# 01_power.net
KiCad netlist of a schematic drawn in Altium Designer
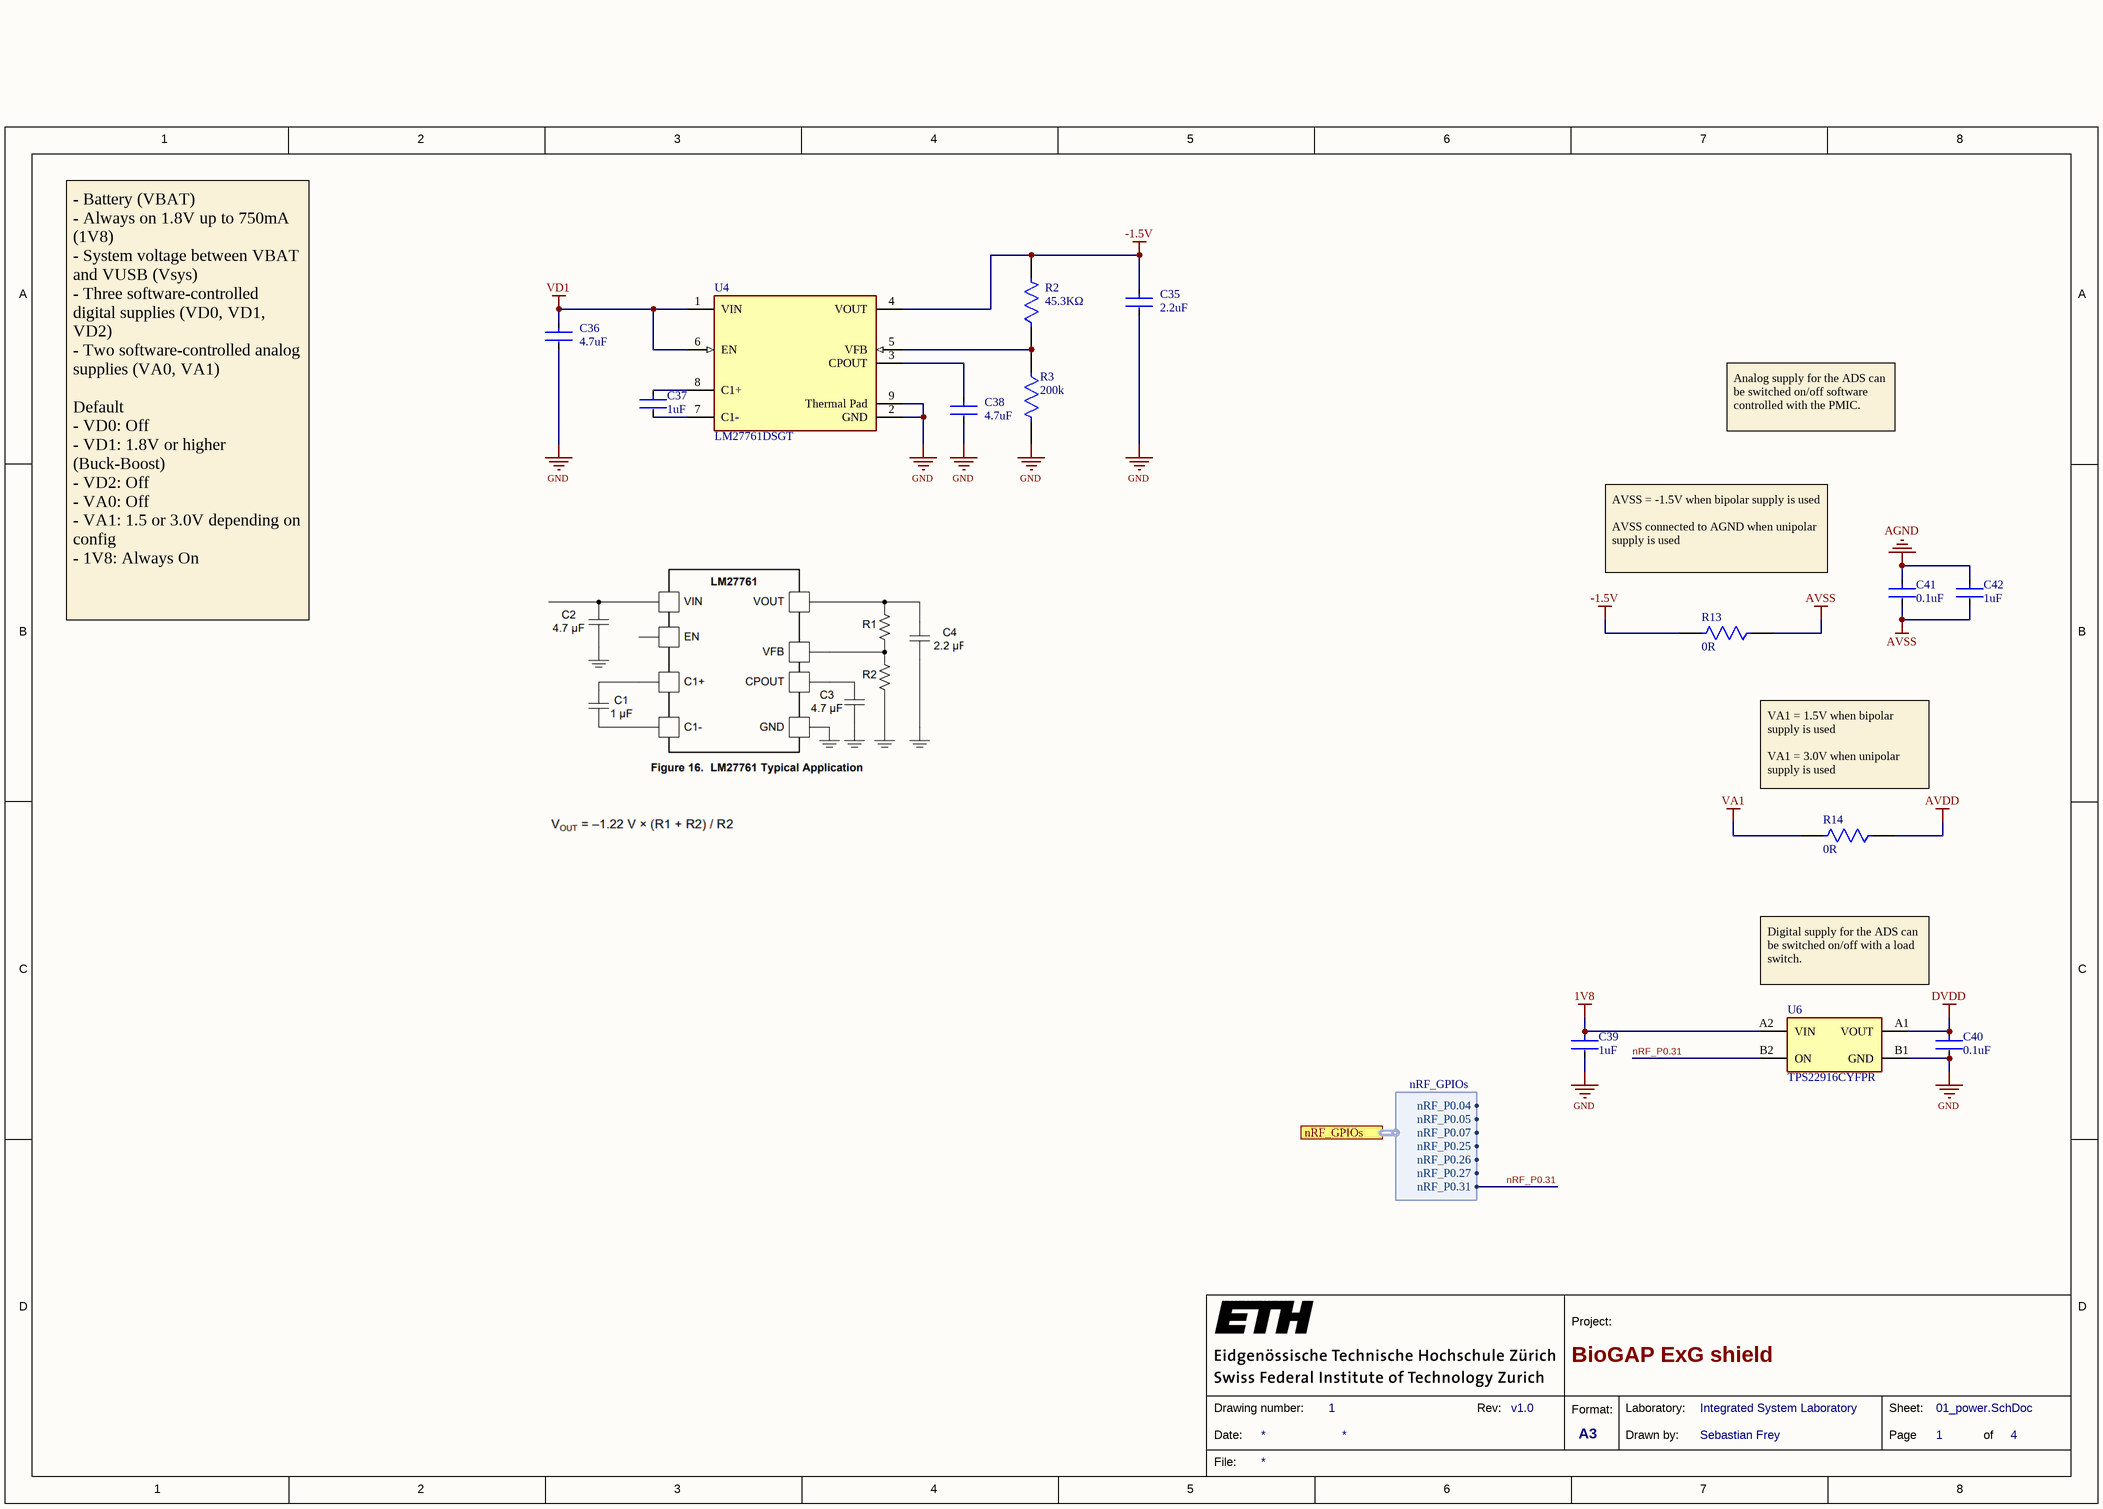
[diagram p0: 01_power.SchDoc]

(export (version "E")
  (design (tool "Eeschema 10.0.6"))
  (components
    (comp (ref "C35")
      (value "GRM155Z71A225KE01D")
      (footprint "FP-GRM155-0_15-IPC_B")
      (description "Chip Multilayer Ceramic Capacitors for General Purpose, 0402, 2.2uF, X7R, 15%, 10%, 10V")
      (fields (field (name "CAPACITANCE") "2.2uF"))
      (libsource (lib "Altium Content Vault") (part "b4654b650e69147ec39a6b967a45e02"))
    )
    (comp (ref "C36")
      (value "CL05A475MP5NRNC")
      (footprint "FP-CL282-IPC_C")
      (description "Cap Ceramic 4.7uF 10V X5R ±20% SMD 0402 +85°C Paper T/R")
      (fields (field (name "CAPACITANCE") "4.7uF") (field (name "TOLERANCE") "20%"))
      (libsource (lib "Altium Content Vault") (part "b4654b650e69147ec39a6b967a45e02"))
    )
    (comp (ref "C37")
      (value "CL05A105KP5NNNC")
      (footprint "FP-CL511-IPC_C")
      (description "Cap Ceramic 1uF 10V X5R ±10% SMD 0402 +85°C Paper T/R")
      (fields (field (name "CAPACITANCE") "1uF") (field (name "TOLERANCE") "10%"))
      (libsource (lib "Altium Content Vault") (part "b4654b650e69147ec39a6b967a45e02"))
    )
    (comp (ref "C38")
      (value "CL05A475MP5NRNC")
      (footprint "FP-CL282-IPC_C")
      (description "Cap Ceramic 4.7uF 10V X5R ±20% SMD 0402 +85°C Paper T/R")
      (fields (field (name "CAPACITANCE") "4.7uF") (field (name "TOLERANCE") "20%"))
      (libsource (lib "Altium Content Vault") (part "b4654b650e69147ec39a6b967a45e02"))
    )
    (comp (ref "C39")
      (value "CL05A105KP5NNNC")
      (footprint "FP-CL511-IPC_C")
      (description "Cap Ceramic 1uF 10V X5R ±10% SMD 0402 +85°C Paper T/R")
      (fields (field (name "CAPACITANCE") "1uF") (field (name "TOLERANCE") "10%"))
      (libsource (lib "Altium Content Vault") (part "b4654b650e69147ec39a6b967a45e02"))
    )
    (comp (ref "C40")
      (value "CL05A104KA5NNNC")
      (footprint "FP-CL278-IPC_C")
      (description "Cap Ceramic 100nF 25V X5R ±10% SMD 0402 +85°C Paper T/R")
      (fields
        (field (name "VOLTAGE") "25V")
        (field (name "TOLERANCE") "10%")
        (field (name "CAPACITANCE") "0.1uF")
      )
      (libsource (lib "Altium Content Vault") (part "b4654b650e69147ec39a6b967a45e02"))
    )
    (comp (ref "C41")
      (value "CL05A104KA5NNNC")
      (footprint "FP-CL278-IPC_C")
      (description "Cap Ceramic 100nF 25V X5R ±10% SMD 0402 +85°C Paper T/R")
      (fields
        (field (name "VOLTAGE") "25V")
        (field (name "TOLERANCE") "10%")
        (field (name "CAPACITANCE") "0.1uF")
      )
      (libsource (lib "Altium Content Vault") (part "b4654b650e69147ec39a6b967a45e02"))
    )
    (comp (ref "C42")
      (value "CL05A105KP5NNNC")
      (footprint "FP-CL511-IPC_C")
      (description "Cap Ceramic 1uF 10V X5R ±10% SMD 0402 +85°C Paper T/R")
      (fields (field (name "CAPACITANCE") "1uF") (field (name "TOLERANCE") "10%"))
      (libsource (lib "Altium Content Vault") (part "b4654b650e69147ec39a6b967a45e02"))
    )
    (comp (ref "R2")
      (value "RT0402BRD0745K3L")
      (footprint "FP-RT0402-MFG")
      (description "RES 45.3K OHM 1/16W .1% SMD 0402")
      (fields
        (field (name "RESISTANCE") "45.3KΩ")
        (field (name "MANUFACTURER") "Yageo")
        (field (name "TOLERANCE") "0.001")
      )
      (libsource (lib "Altium Content Vault") (part "1029c3af85768c4190bb7ad29bc67b5"))
    )
    (comp (ref "R3")
      (value "RN73R1ETTP2003B25")
      (footprint "FP-RN73R1E-IPC_C")
      (description "200kΩ ±0.1% 0.063W, 1/16W Chip Resistor 0402 (1005 Metric) Moisture Resistant Thin Film")
      (fields (field (name "RESISTANCE") "200k"))
      (libsource (lib "Altium Content Vault") (part "1029c3af85768c4190bb7ad29bc67b5"))
    )
    (comp (ref "R13")
      (value "RC0402FR-070RL")
      (footprint "FP-RC0402-0_4-IPC_A")
      (description "RES SMD 0 OHM JUMPER 1/16W 0402")
      (fields (field (name "RESISTANCE") "0R") (field (name "TOLERANCE") "1%"))
      (libsource (lib "Altium Content Vault") (part "1029c3af85768c4190bb7ad29bc67b5"))
    )
    (comp (ref "R14")
      (value "RC0402FR-070RL")
      (footprint "FP-RC0402-0_4-IPC_A")
      (description "RES SMD 0 OHM JUMPER 1/16W 0402")
      (fields (field (name "RESISTANCE") "0R") (field (name "TOLERANCE") "1%"))
      (libsource (lib "Altium Content Vault") (part "1029c3af85768c4190bb7ad29bc67b5"))
    )
    (comp (ref "U4")
      (value "LM27761DSGT")
      (footprint "FP-DSG0008A-MFG")
      (description "IC REG CHARGE PUMP ADJ 8WSON")
      (fields
        (field (name "MANUFACTURER") "Texas Instruments")
        (field (name "OCTOPART") "https://octopart.com/lm27761dsgt-texas+instruments-66646294")
      )
      (libsource (lib "Altium Content Vault") (part "53c421dca18d0755d6b27e0601e0b83"))
    )
    (comp (ref "U6")
      (value "TPS22916CYFPR")
      (footprint "SamacSys:BGA4C40P2X2_78X78X50")
      (description "Integrated Circuit")
      (fields (field (name "MOUSER PART NUMBER") "595-TPS22916CYFPR"))
      (libsource (lib "SamacSys") (part "TPS22916CYFPR"))
    )
  )
  (nets
    (net (code "2") (name "-1.5V") (class "Default")
      (node (ref "C35") (pin "1") (pinfunction "1_1") (pintype "passive"))
      (node (ref "R13") (pin "2") (pinfunction "2_2") (pintype "passive"))
      (node (ref "R2") (pin "2") (pinfunction "2_2") (pintype "passive"))
      (node (ref "U4") (pin "4") (pinfunction "VOUT_4") (pintype "passive"))
    )
    (net (code "3") (name "/nRF_P0.31") (class "Default")
      (node (ref "U6") (pin "B2") (pinfunction "ON_B2") (pintype "passive"))
    )
    (net (code "5") (name "1V8") (class "Default")
      (node (ref "C39") (pin "1") (pinfunction "1_1") (pintype "passive"))
      (node (ref "U6") (pin "A2") (pinfunction "VIN_A2") (pintype "passive"))
    )
    (net (code "6") (name "AGND") (class "Default")
      (node (ref "C41") (pin "1") (pinfunction "1_1") (pintype "passive"))
      (node (ref "C42") (pin "1") (pinfunction "1_1") (pintype "passive"))
    )
    (net (code "7") (name "AVDD") (class "Default")
      (node (ref "R14") (pin "1") (pinfunction "1_1") (pintype "passive"))
    )
    (net (code "8") (name "AVSS") (class "Default")
      (node (ref "C41") (pin "2") (pinfunction "2_2") (pintype "passive"))
      (node (ref "C42") (pin "2") (pinfunction "2_2") (pintype "passive"))
      (node (ref "R13") (pin "1") (pinfunction "1_1") (pintype "passive"))
    )
    (net (code "9") (name "DVDD") (class "Default")
      (node (ref "C40") (pin "1") (pinfunction "1_1") (pintype "passive"))
      (node (ref "U6") (pin "A1") (pinfunction "VOUT_A1") (pintype "passive"))
    )
    (net (code "10") (name "GND") (class "Default")
      (node (ref "C35") (pin "2") (pinfunction "2_2") (pintype "passive"))
      (node (ref "C36") (pin "2") (pinfunction "2_2") (pintype "passive"))
      (node (ref "C38") (pin "2") (pinfunction "2_2") (pintype "passive"))
      (node (ref "C39") (pin "2") (pinfunction "2_2") (pintype "passive"))
      (node (ref "C40") (pin "2") (pinfunction "2_2") (pintype "passive"))
      (node (ref "R3") (pin "2") (pinfunction "2_2") (pintype "passive"))
      (node (ref "U4") (pin "2") (pinfunction "GND_2") (pintype "power_in"))
      (node (ref "U4") (pin "9") (pinfunction "Thermal_Pad_9") (pintype "power_in"))
      (node (ref "U6") (pin "B1") (pinfunction "GND_B1") (pintype "passive"))
    )
    (net (code "11") (name "Net-(U4-C1+)") (class "Default")
      (node (ref "C37") (pin "1") (pinfunction "1_1") (pintype "passive"))
      (node (ref "U4") (pin "8") (pinfunction "C1+_8") (pintype "passive"))
    )
    (net (code "12") (name "Net-(U4-C1-)") (class "Default")
      (node (ref "C37") (pin "2") (pinfunction "2_2") (pintype "passive"))
      (node (ref "U4") (pin "7") (pinfunction "C1-_7") (pintype "passive"))
    )
    (net (code "13") (name "Net-(U4-CPOUT)") (class "Default")
      (node (ref "C38") (pin "1") (pinfunction "1_1") (pintype "passive"))
      (node (ref "U4") (pin "3") (pinfunction "CPOUT_3") (pintype "passive"))
    )
    (net (code "14") (name "Net-(U4-VFB)") (class "Default")
      (node (ref "R2") (pin "1") (pinfunction "1_1") (pintype "passive"))
      (node (ref "R3") (pin "1") (pinfunction "1_1") (pintype "passive"))
      (node (ref "U4") (pin "5") (pinfunction "VFB_5") (pintype "input"))
    )
    (net (code "15") (name "VA1") (class "Default")
      (node (ref "R14") (pin "2") (pinfunction "2_2") (pintype "passive"))
    )
    (net (code "16") (name "VD1") (class "Default")
      (node (ref "C36") (pin "1") (pinfunction "1_1") (pintype "passive"))
      (node (ref "U4") (pin "1") (pinfunction "VIN_1") (pintype "power_in"))
      (node (ref "U4") (pin "6") (pinfunction "EN_6") (pintype "input"))
    )
  )
)
